# IR_Range.net
KiCad netlist of a schematic drawn in Altium Designer
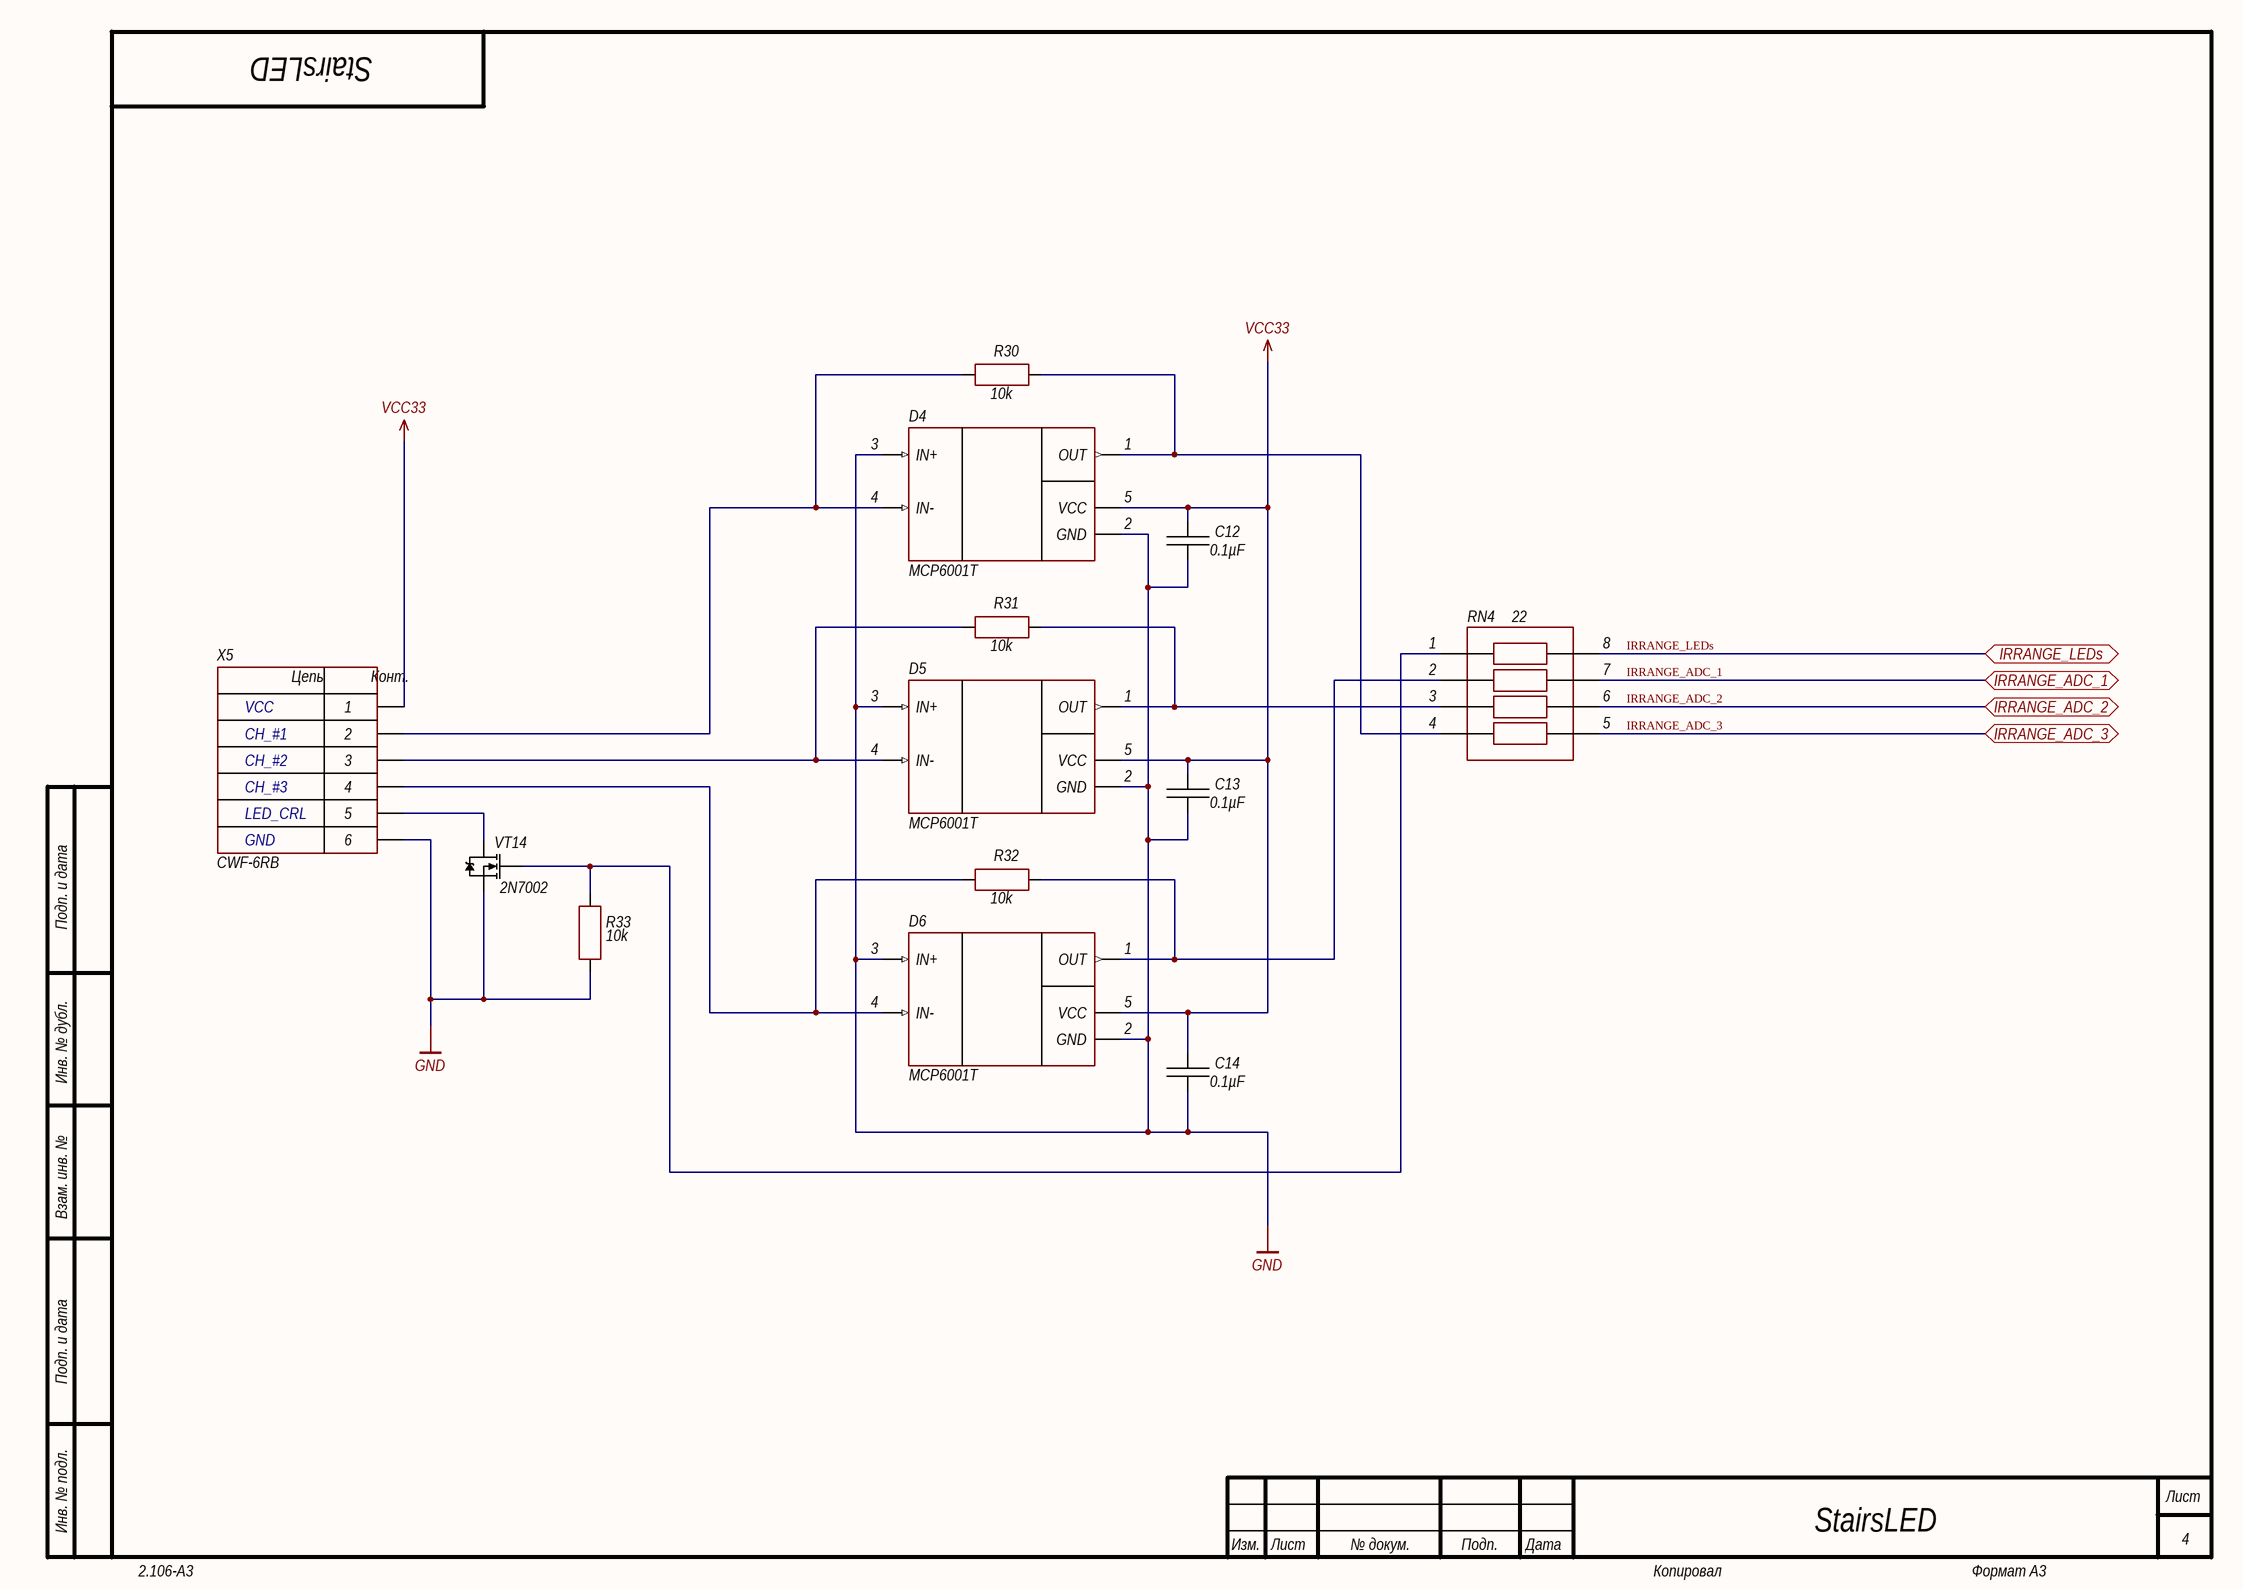
[diagram p0: IR Range.SchDoc]

(export (version "E")
  (design (tool "Eeschema 10.0.6"))
  (components
    (comp (ref "C12") (value "0.1µF") (footprint "CH0603C") (libsource (lib "Discrete") (part "Capacitor")))
    (comp (ref "C13") (value "0.1µF") (footprint "CH0603C") (libsource (lib "Discrete") (part "Capacitor")))
    (comp (ref "C14") (value "0.1µF") (footprint "CH0603C") (libsource (lib "Discrete") (part "Capacitor")))
    (comp (ref "D4")
      (value "MCP6001T")
      (footprint "SOT23-5")
      (description "OP amplifier")
      (fields (field (name "MANUFACTURER") "Microchip Technology"))
      (libsource (lib "Analog") (part "MCP6001T"))
    )
    (comp (ref "D5")
      (value "MCP6001T")
      (footprint "SOT23-5")
      (description "OP amplifier")
      (fields (field (name "MANUFACTURER") "Microchip Technology"))
      (libsource (lib "Analog") (part "MCP6001T"))
    )
    (comp (ref "D6")
      (value "MCP6001T")
      (footprint "SOT23-5")
      (description "OP amplifier")
      (fields (field (name "MANUFACTURER") "Microchip Technology"))
      (libsource (lib "Analog") (part "MCP6001T"))
    )
    (comp (ref "R30") (value "10k") (footprint "CH0603R") (libsource (lib "Discrete") (part "Resistor")))
    (comp (ref "R31") (value "10k") (footprint "CH0603R") (libsource (lib "Discrete") (part "Resistor")))
    (comp (ref "R32") (value "10k") (footprint "CH0603R") (libsource (lib "Discrete") (part "Resistor")))
    (comp (ref "R33") (value "10k") (footprint "CH0603R") (libsource (lib "") (part "Resistor_1")))
    (comp (ref "RN4")
      (value "22")
      (footprint "CH0603Rx4 (1206)")
      (fields (field (name "MANUFACTURER") "Bourns GmbH."))
      (libsource (lib "Discrete") (part "Resistor assembly"))
    )
    (comp (ref "VT14")
      (value "2N7002")
      (footprint "SOT23_132")
      (description "Mosfet")
      (fields (field (name "MANUFACTURER") "ON Semiconductor"))
      (libsource (lib "Transistor") (part "N-chanel"))
    )
    (comp (ref "X5")
      (value "CWF-6RB")
      (footprint "CON: CWF-6RB")
      (libsource (lib "Connectors") (part "6-Connector"))
    )
  )
  (nets
    (net (code "1") (name "/IRRANGE_ADC_1") (class "Default")
      (node (ref "RN4") (pin "7") (pinfunction "7_7") (pintype "passive"))
    )
    (net (code "2") (name "/IRRANGE_ADC_2") (class "Default")
      (node (ref "RN4") (pin "6") (pinfunction "6_6") (pintype "passive"))
    )
    (net (code "3") (name "/IRRANGE_ADC_3") (class "Default")
      (node (ref "RN4") (pin "5") (pinfunction "5_5") (pintype "passive"))
    )
    (net (code "4") (name "/IRRANGE_LEDs") (class "Default")
      (node (ref "RN4") (pin "8") (pinfunction "8_8") (pintype "passive"))
    )
    (net (code "5") (name "GND") (class "Default")
      (node (ref "C12") (pin "1") (pinfunction "1_1") (pintype "power_in"))
      (node (ref "C13") (pin "1") (pinfunction "1_1") (pintype "power_in"))
      (node (ref "C14") (pin "1") (pinfunction "1_1") (pintype "power_in"))
      (node (ref "D4") (pin "2") (pinfunction "GND_2") (pintype "power_in"))
      (node (ref "D4") (pin "3") (pinfunction "IN+_3") (pintype "input"))
      (node (ref "D5") (pin "2") (pinfunction "GND_2") (pintype "power_in"))
      (node (ref "D5") (pin "3") (pinfunction "IN+_3") (pintype "input"))
      (node (ref "D6") (pin "2") (pinfunction "GND_2") (pintype "power_in"))
      (node (ref "D6") (pin "3") (pinfunction "IN+_3") (pintype "input"))
      (node (ref "R33") (pin "1") (pinfunction "1_1") (pintype "passive"))
      (node (ref "VT14") (pin "3") (pinfunction "S_3") (pintype "passive"))
      (node (ref "X5") (pin "6") (pinfunction "6_6") (pintype "power_in"))
    )
    (net (code "6") (name "Net-(D4-IN-)") (class "Default")
      (node (ref "D4") (pin "4") (pinfunction "IN-_4") (pintype "input"))
      (node (ref "R30") (pin "1") (pinfunction "1_1") (pintype "passive"))
      (node (ref "X5") (pin "2") (pinfunction "2_2") (pintype "passive"))
    )
    (net (code "7") (name "Net-(D4-OUT)") (class "Default")
      (node (ref "D4") (pin "1") (pinfunction "OUT_1") (pintype "output"))
      (node (ref "R30") (pin "2") (pinfunction "2_2") (pintype "passive"))
      (node (ref "RN4") (pin "4") (pinfunction "4_4") (pintype "passive"))
    )
    (net (code "8") (name "Net-(D5-IN-)") (class "Default")
      (node (ref "D5") (pin "4") (pinfunction "IN-_4") (pintype "input"))
      (node (ref "R31") (pin "1") (pinfunction "1_1") (pintype "passive"))
      (node (ref "X5") (pin "3") (pinfunction "3_3") (pintype "power_in"))
    )
    (net (code "9") (name "Net-(D5-OUT)") (class "Default")
      (node (ref "D5") (pin "1") (pinfunction "OUT_1") (pintype "output"))
      (node (ref "R31") (pin "2") (pinfunction "2_2") (pintype "passive"))
      (node (ref "RN4") (pin "3") (pinfunction "3_3") (pintype "passive"))
    )
    (net (code "10") (name "Net-(D6-IN-)") (class "Default")
      (node (ref "D6") (pin "4") (pinfunction "IN-_4") (pintype "input"))
      (node (ref "R32") (pin "1") (pinfunction "1_1") (pintype "passive"))
      (node (ref "X5") (pin "4") (pinfunction "4_4") (pintype "power_in"))
    )
    (net (code "11") (name "Net-(D6-OUT)") (class "Default")
      (node (ref "D6") (pin "1") (pinfunction "OUT_1") (pintype "output"))
      (node (ref "R32") (pin "2") (pinfunction "2_2") (pintype "passive"))
      (node (ref "RN4") (pin "2") (pinfunction "2_2") (pintype "passive"))
    )
    (net (code "12") (name "Net-(VT14-D)") (class "Default")
      (node (ref "VT14") (pin "2") (pinfunction "D_2") (pintype "passive"))
      (node (ref "X5") (pin "5") (pinfunction "5_5") (pintype "power_in"))
    )
    (net (code "13") (name "Net-(VT14-G)") (class "Default")
      (node (ref "R33") (pin "2") (pinfunction "2_2") (pintype "passive"))
      (node (ref "RN4") (pin "1") (pinfunction "1_1") (pintype "passive"))
      (node (ref "VT14") (pin "1") (pinfunction "G_1") (pintype "passive"))
    )
    (net (code "14") (name "VCC33") (class "Default")
      (node (ref "C12") (pin "2") (pinfunction "2_2") (pintype "power_in"))
      (node (ref "C13") (pin "2") (pinfunction "2_2") (pintype "power_in"))
      (node (ref "C14") (pin "2") (pinfunction "2_2") (pintype "power_in"))
      (node (ref "D4") (pin "5") (pinfunction "VCC_5") (pintype "power_in"))
      (node (ref "D5") (pin "5") (pinfunction "VCC_5") (pintype "power_in"))
      (node (ref "D6") (pin "5") (pinfunction "VCC_5") (pintype "power_in"))
      (node (ref "X5") (pin "1") (pinfunction "1_1") (pintype "passive"))
    )
  )
)
